# Polarshield_v1_6.net
KiCad netlist of a schematic drawn in EAGLE
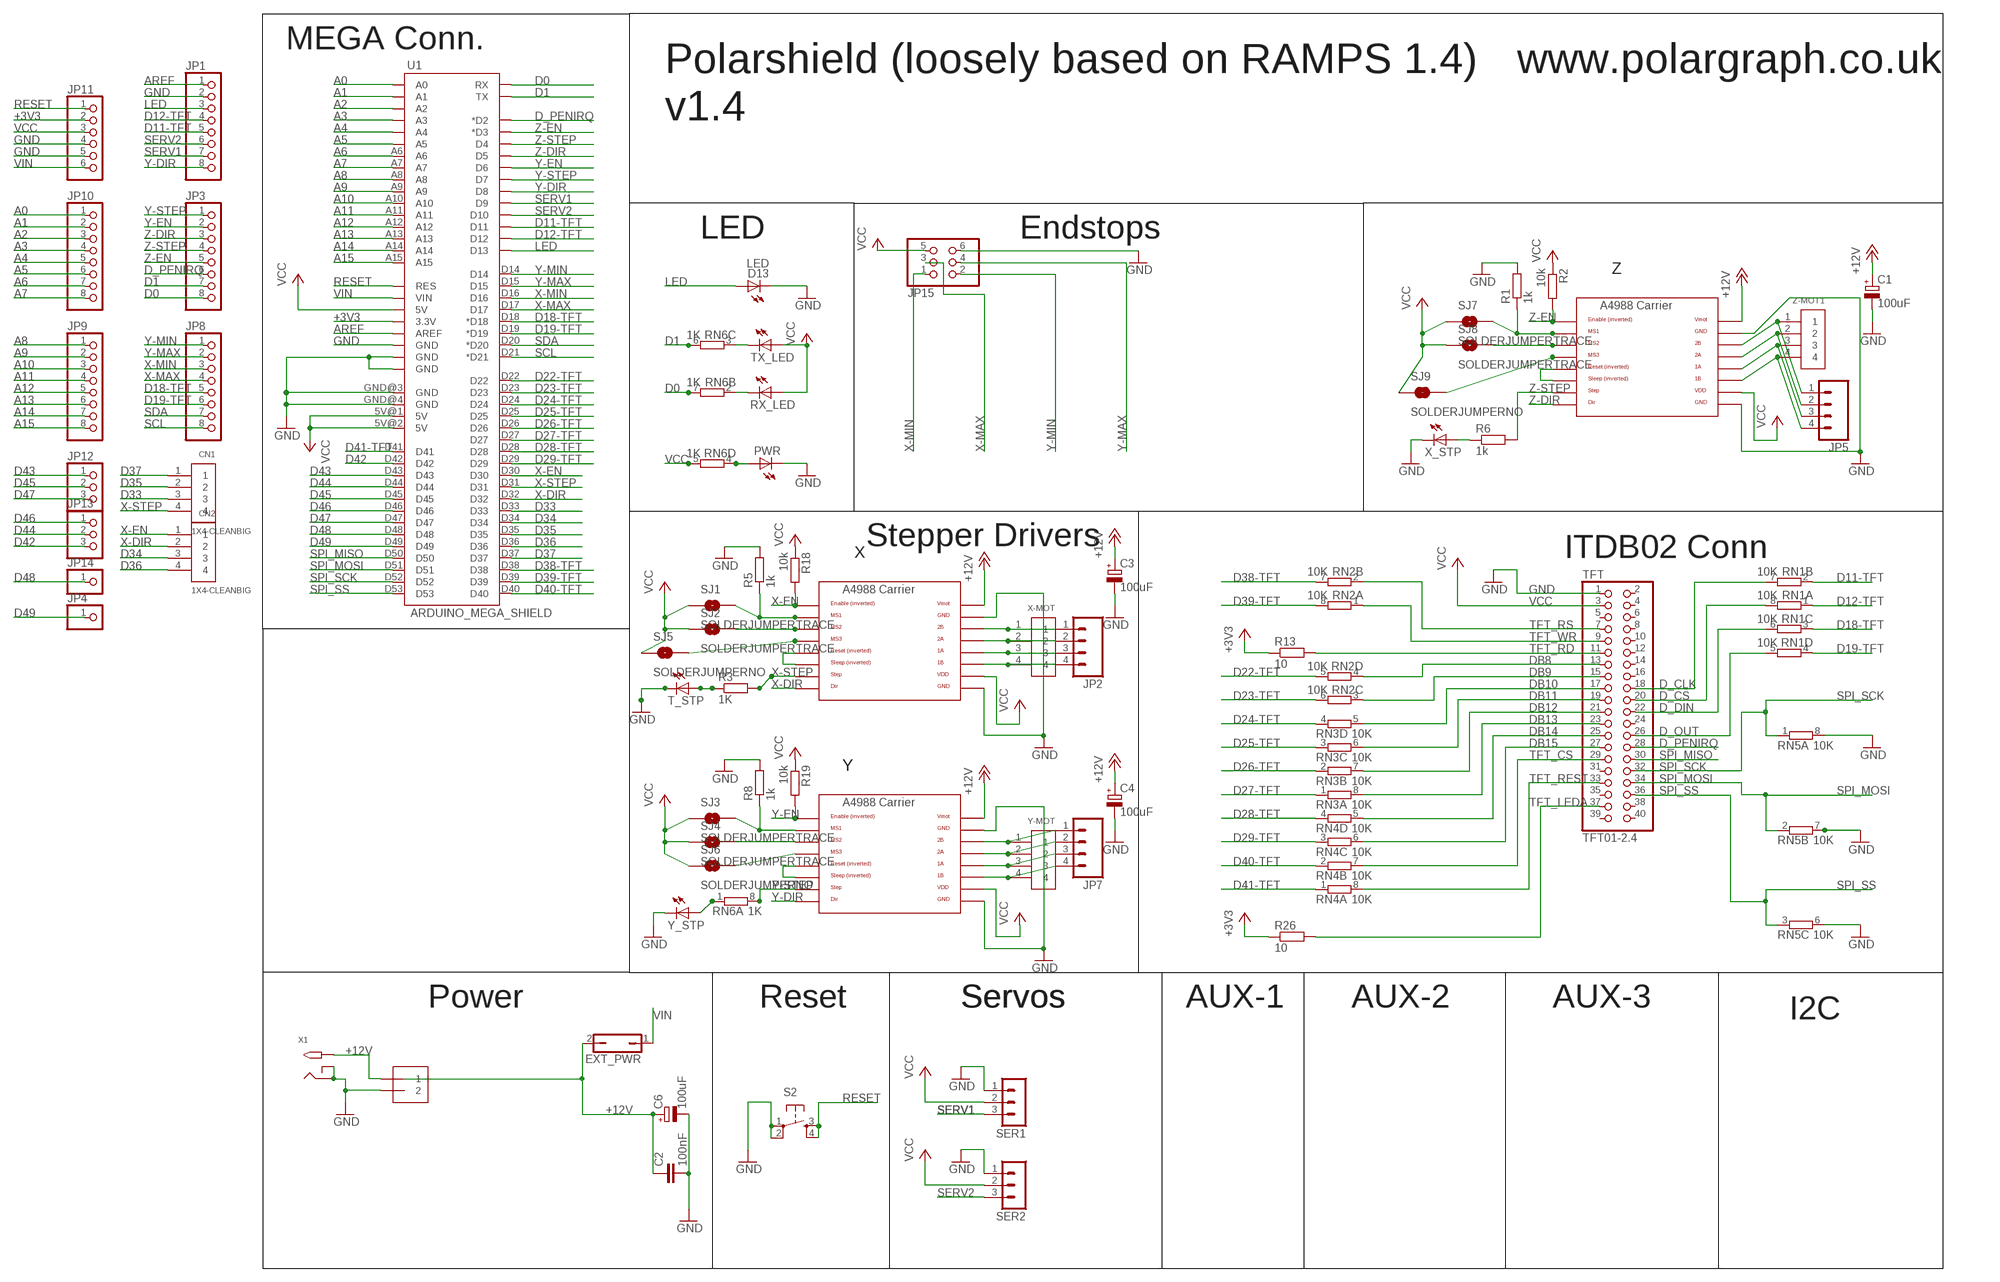
[diagram p0: schematic, sheet 1]

(export (version "E")
  (design (tool "Eeschema 10.0.6"))
  (components
    (comp (ref "C1")
      (value "100uF")
      (footprint "eagle-import:153CLV-0605")
      (libsource (lib "eagle-import") (part "CPOL-EU153CLV-0605"))
    )
    (comp (ref "C2")
      (value "100nF")
      (footprint "eagle-import:C0805")
      (libsource (lib "eagle-import") (part "C-EUC0805"))
    )
    (comp (ref "C3")
      (value "100uF")
      (footprint "eagle-import:153CLV-0605")
      (libsource (lib "eagle-import") (part "CPOL-EU153CLV-0605"))
    )
    (comp (ref "C4")
      (value "100uF")
      (footprint "eagle-import:153CLV-0605")
      (libsource (lib "eagle-import") (part "CPOL-EU153CLV-0605"))
    )
    (comp (ref "C6")
      (value "100uF")
      (footprint "eagle-import:153CLV-0605")
      (libsource (lib "eagle-import") (part "CPOL-EU153CLV-0605"))
    )
    (comp (ref "CN1")
      (value "1X4-CLEANBIG")
      (footprint "eagle-import:1X04-CLEANBIG")
      (libsource (lib "eagle-import") (part "1X4-CLEANBIG"))
    )
    (comp (ref "CN2")
      (value "1X4-CLEANBIG")
      (footprint "eagle-import:1X04-CLEANBIG")
      (libsource (lib "eagle-import") (part "1X4-CLEANBIG"))
    )
    (comp (ref "D13")
      (value "LED")
      (footprint "eagle-import:CHIP-LED0805")
      (libsource (lib "eagle-import") (part "LEDCHIP-LED0805"))
    )
    (comp (ref "EXT_PWR")
      (value "JP1Q")
      (footprint "eagle-import:JP1")
      (libsource (lib "eagle-import") (part "JP1Q"))
    )
    (comp (ref "J1")
      (value "1X2-3.5MM")
      (footprint "eagle-import:1X2-3.5MM")
      (libsource (lib "eagle-import") (part "1X2-3.5MM"))
    )
    (comp (ref "JP1")
      (value "PINHD-1X8CLEANBIG")
      (footprint "eagle-import:1X08-CLEANBIG")
      (libsource (lib "eagle-import") (part "PINHD-1X8CLEANBIG"))
    )
    (comp (ref "JP2")
      (value "M04SCREW")
      (footprint "eagle-import:SCREWTERMINAL-3.5MM-4")
      (libsource (lib "eagle-import") (part "M04SCREW"))
    )
    (comp (ref "JP3")
      (value "PINHD-1X8CLEANBIG")
      (footprint "eagle-import:1X08-CLEANBIG")
      (libsource (lib "eagle-import") (part "PINHD-1X8CLEANBIG"))
    )
    (comp (ref "JP4")
      (value "PINHD-1X1CB")
      (footprint "eagle-import:1X01-CLEANBIG")
      (libsource (lib "eagle-import") (part "PINHD-1X1CB"))
    )
    (comp (ref "JP5")
      (value "M04SCREW")
      (footprint "eagle-import:SCREWTERMINAL-3.5MM-4")
      (libsource (lib "eagle-import") (part "M04SCREW"))
    )
    (comp (ref "JP7")
      (value "M04SCREW")
      (footprint "eagle-import:SCREWTERMINAL-3.5MM-4")
      (libsource (lib "eagle-import") (part "M04SCREW"))
    )
    (comp (ref "JP8")
      (value "PINHD-1X8CLEANBIG")
      (footprint "eagle-import:1X08-CLEANBIG")
      (libsource (lib "eagle-import") (part "PINHD-1X8CLEANBIG"))
    )
    (comp (ref "JP9")
      (value "PINHD-1X8CLEANBIG")
      (footprint "eagle-import:1X08-CLEANBIG")
      (libsource (lib "eagle-import") (part "PINHD-1X8CLEANBIG"))
    )
    (comp (ref "JP10")
      (value "PINHD-1X8CLEANBIG")
      (footprint "eagle-import:1X08-CLEANBIG")
      (libsource (lib "eagle-import") (part "PINHD-1X8CLEANBIG"))
    )
    (comp (ref "JP11")
      (value "PINHD-1X6CB")
      (footprint "eagle-import:1X06-CLEANBIG")
      (libsource (lib "eagle-import") (part "PINHD-1X6CB"))
    )
    (comp (ref "JP12")
      (value "PINHD-1X3CB")
      (footprint "eagle-import:1X03-CLEANBIG")
      (libsource (lib "eagle-import") (part "PINHD-1X3CB"))
    )
    (comp (ref "JP13")
      (value "PINHD-1X3CB")
      (footprint "eagle-import:1X03-CLEANBIG")
      (libsource (lib "eagle-import") (part "PINHD-1X3CB"))
    )
    (comp (ref "JP14")
      (value "PINHD-1X1CB")
      (footprint "eagle-import:1X01-CLEANBIG")
      (libsource (lib "eagle-import") (part "PINHD-1X1CB"))
    )
    (comp (ref "JP15")
      (value "PINHD-2X3")
      (footprint "eagle-import:2X03")
      (libsource (lib "eagle-import") (part "PINHD-2X3"))
    )
    (comp (ref "PWR")
      (value "LEDCHIP-LED0805")
      (footprint "eagle-import:CHIP-LED0805")
      (libsource (lib "eagle-import") (part "LEDCHIP-LED0805"))
    )
    (comp (ref "R1")
      (value "1k")
      (footprint "eagle-import:R0805")
      (libsource (lib "eagle-import") (part "R-EU_R0805"))
    )
    (comp (ref "R2")
      (value "10k")
      (footprint "eagle-import:R0805")
      (libsource (lib "eagle-import") (part "R-EU_R0805"))
    )
    (comp (ref "R3")
      (value "1K")
      (footprint "eagle-import:R0805")
      (libsource (lib "eagle-import") (part "R-EU_R0805"))
    )
    (comp (ref "R5")
      (value "1k")
      (footprint "eagle-import:R0805")
      (libsource (lib "eagle-import") (part "R-EU_R0805"))
    )
    (comp (ref "R6")
      (value "1k")
      (footprint "eagle-import:R0805")
      (libsource (lib "eagle-import") (part "R-EU_R0805"))
    )
    (comp (ref "R8")
      (value "1k")
      (footprint "eagle-import:R0805")
      (libsource (lib "eagle-import") (part "R-EU_R0805"))
    )
    (comp (ref "R13")
      (value "10")
      (footprint "eagle-import:R0805")
      (libsource (lib "eagle-import") (part "resistor_R-EU_R0805"))
    )
    (comp (ref "R18")
      (value "10k")
      (footprint "eagle-import:R0805")
      (libsource (lib "eagle-import") (part "R-EU_R0805"))
    )
    (comp (ref "R19")
      (value "10k")
      (footprint "eagle-import:R0805")
      (libsource (lib "eagle-import") (part "R-EU_R0805"))
    )
    (comp (ref "R26")
      (value "10")
      (footprint "eagle-import:R0805")
      (libsource (lib "eagle-import") (part "resistor_R-EU_R0805"))
    )
    (comp (ref "RN1")
      (value "10K")
      (footprint "eagle-import:EXBS8V")
      (libsource (lib "eagle-import") (part "4R-NEXBS8V"))
    )
    (comp (ref "RN2")
      (value "10K")
      (footprint "eagle-import:EXBS8V")
      (libsource (lib "eagle-import") (part "4R-NEXBS8V"))
    )
    (comp (ref "RN3")
      (value "10K")
      (footprint "eagle-import:EXBS8V")
      (libsource (lib "eagle-import") (part "4R-NEXBS8V"))
    )
    (comp (ref "RN4")
      (value "10K")
      (footprint "eagle-import:EXBS8V")
      (libsource (lib "eagle-import") (part "4R-NEXBS8V"))
    )
    (comp (ref "RN5")
      (value "10K")
      (footprint "eagle-import:EXBS8V")
      (libsource (lib "eagle-import") (part "4R-NEXBS8V"))
    )
    (comp (ref "RN6")
      (value "1K")
      (footprint "eagle-import:EXBS8V")
      (libsource (lib "eagle-import") (part "4R-NEXBS8V"))
    )
    (comp (ref "RX_LED")
      (value "LEDCHIP-LED0805")
      (footprint "eagle-import:CHIP-LED0805")
      (libsource (lib "eagle-import") (part "LEDCHIP-LED0805"))
    )
    (comp (ref "S2")
      (value "TAC_SWITCHPTH")
      (footprint "eagle-import:TACTILE-PTH")
      (libsource (lib "eagle-import") (part "TAC_SWITCHPTH"))
    )
    (comp (ref "SER1")
      (value "3PIN-HEADER")
      (footprint "eagle-import:3PIN-HEADER")
      (libsource (lib "eagle-import") (part "3PIN-HEADER"))
    )
    (comp (ref "SER2")
      (value "3PIN-HEADER")
      (footprint "eagle-import:3PIN-HEADER")
      (libsource (lib "eagle-import") (part "3PIN-HEADER"))
    )
    (comp (ref "SJ1")
      (value "SOLDERJUMPERTRACE")
      (footprint "eagle-import:SJ_2S-TRACE")
      (libsource (lib "eagle-import") (part "SOLDERJUMPERTRACE"))
    )
    (comp (ref "SJ2")
      (value "SOLDERJUMPERTRACE")
      (footprint "eagle-import:SJ_2S-TRACE")
      (libsource (lib "eagle-import") (part "SOLDERJUMPERTRACE"))
    )
    (comp (ref "SJ3")
      (value "SOLDERJUMPERTRACE")
      (footprint "eagle-import:SJ_2S-TRACE")
      (libsource (lib "eagle-import") (part "SOLDERJUMPERTRACE"))
    )
    (comp (ref "SJ4")
      (value "SOLDERJUMPERTRACE")
      (footprint "eagle-import:SJ_2S-TRACE")
      (libsource (lib "eagle-import") (part "SOLDERJUMPERTRACE"))
    )
    (comp (ref "SJ5")
      (value "SOLDERJUMPERNO")
      (footprint "eagle-import:SJ_2S-NO")
      (libsource (lib "eagle-import") (part "SOLDERJUMPERNO"))
    )
    (comp (ref "SJ6")
      (value "SOLDERJUMPERNO")
      (footprint "eagle-import:SJ_2S-NO")
      (libsource (lib "eagle-import") (part "SOLDERJUMPERNO"))
    )
    (comp (ref "SJ7")
      (value "SOLDERJUMPERTRACE")
      (footprint "eagle-import:SJ_2S-TRACE")
      (libsource (lib "eagle-import") (part "SOLDERJUMPERTRACE"))
    )
    (comp (ref "SJ8")
      (value "SOLDERJUMPERTRACE")
      (footprint "eagle-import:SJ_2S-TRACE")
      (libsource (lib "eagle-import") (part "SOLDERJUMPERTRACE"))
    )
    (comp (ref "SJ9")
      (value "SOLDERJUMPERNO")
      (footprint "eagle-import:SJ_2S-NO")
      (libsource (lib "eagle-import") (part "SOLDERJUMPERNO"))
    )
    (comp (ref "TFT")
      (value "TFT01-2.4")
      (footprint "eagle-import:TFT01-2.4")
      (libsource (lib "eagle-import") (part "TFT01-2.4"))
    )
    (comp (ref "TX_LED")
      (value "LEDCHIP-LED0805")
      (footprint "eagle-import:CHIP-LED0805")
      (libsource (lib "eagle-import") (part "LEDCHIP-LED0805"))
    )
    (comp (ref "T_STP")
      (value "LEDCHIP-LED0805")
      (footprint "eagle-import:CHIP-LED0805")
      (libsource (lib "eagle-import") (part "LEDCHIP-LED0805"))
    )
    (comp (ref "U$1")
      (value "A4988BREAKOUT")
      (footprint "eagle-import:A4988BREAKOUT")
      (libsource (lib "eagle-import") (part "A4988BREAKOUT"))
    )
    (comp (ref "U$6")
      (value "A4988BREAKOUT")
      (footprint "eagle-import:A4988BREAKOUT")
      (libsource (lib "eagle-import") (part "A4988BREAKOUT"))
    )
    (comp (ref "U$7")
      (value "A4988BREAKOUT")
      (footprint "eagle-import:A4988BREAKOUT")
      (libsource (lib "eagle-import") (part "A4988BREAKOUT"))
    )
    (comp (ref "U1")
      (value "ARDUINO_MEGA_SHIELD")
      (footprint "eagle-import:ARDUINO_MEGA_SHIELD")
      (libsource (lib "eagle-import") (part "ARDUINO_MEGA_SHIELD"))
    )
    (comp (ref "X-MOT")
      (value "1X4-BIG")
      (footprint "eagle-import:1X04-BIG")
      (libsource (lib "eagle-import") (part "1X4-BIG"))
    )
    (comp (ref "X1")
      (value "2.1MMJACKTHM")
      (footprint "eagle-import:PJ-102A")
      (libsource (lib "eagle-import") (part "2.1MMJACKTHM"))
    )
    (comp (ref "X_STP")
      (value "LEDCHIP-LED0805")
      (footprint "eagle-import:CHIP-LED0805")
      (libsource (lib "eagle-import") (part "LEDCHIP-LED0805"))
    )
    (comp (ref "Y-MOT")
      (value "1X4-BIG")
      (footprint "eagle-import:1X04-BIG")
      (libsource (lib "eagle-import") (part "1X4-BIG"))
    )
    (comp (ref "Y_STP")
      (value "LEDCHIP-LED0805")
      (footprint "eagle-import:CHIP-LED0805")
      (libsource (lib "eagle-import") (part "LEDCHIP-LED0805"))
    )
    (comp (ref "Z-MOT1")
      (value "1X4-BIG")
      (footprint "eagle-import:1X04-BIG")
      (libsource (lib "eagle-import") (part "1X4-BIG"))
    )
  )
  (nets
    (net (code "1") (name "+3V3") (class "Default")
      (node (ref "JP11") (pin "2") (pinfunction "2_2") (pintype "passive"))
      (node (ref "R13") (pin "1") (pinfunction "1_1") (pintype "passive"))
      (node (ref "R26") (pin "1") (pinfunction "1_1") (pintype "passive"))
      (node (ref "U1") (pin "3.3V") (pinfunction "3.3V_3.3V") (pintype "bidirectional"))
    )
    (net (code "2") (name "+12V") (class "Default")
      (node (ref "C1") (pin "+") (pinfunction "+_+") (pintype "passive"))
      (node (ref "C2") (pin "1") (pinfunction "1_1") (pintype "passive"))
      (node (ref "C3") (pin "+") (pinfunction "+_+") (pintype "passive"))
      (node (ref "C4") (pin "+") (pinfunction "+_+") (pintype "passive"))
      (node (ref "C6") (pin "+") (pinfunction "+_+") (pintype "passive"))
      (node (ref "EXT_PWR") (pin "2") (pinfunction "2_2") (pintype "passive"))
      (node (ref "J1") (pin "1") (pinfunction "1_1") (pintype "passive"))
      (node (ref "U$1") (pin "VMOT") (pinfunction "VMOT_VMOT") (pintype "power_in"))
      (node (ref "U$6") (pin "VMOT") (pinfunction "VMOT_VMOT") (pintype "power_in"))
      (node (ref "U$7") (pin "VMOT") (pinfunction "VMOT_VMOT") (pintype "power_in"))
      (node (ref "X1") (pin "TIP") (pinfunction "TIP_TIP") (pintype "bidirectional"))
    )
    (net (code "3") (name "/A0") (class "Default")
      (node (ref "JP10") (pin "1") (pinfunction "1_1") (pintype "passive"))
      (node (ref "U1") (pin "A0") (pinfunction "A0_A0") (pintype "bidirectional"))
    )
    (net (code "4") (name "/A1") (class "Default")
      (node (ref "JP10") (pin "2") (pinfunction "2_2") (pintype "passive"))
      (node (ref "U1") (pin "A1") (pinfunction "A1_A1") (pintype "bidirectional"))
    )
    (net (code "5") (name "/A2") (class "Default")
      (node (ref "JP10") (pin "3") (pinfunction "3_3") (pintype "passive"))
      (node (ref "U1") (pin "A2") (pinfunction "A2_A2") (pintype "bidirectional"))
    )
    (net (code "6") (name "/A3") (class "Default")
      (node (ref "JP10") (pin "4") (pinfunction "4_4") (pintype "passive"))
      (node (ref "U1") (pin "A3") (pinfunction "A3_A3") (pintype "bidirectional"))
    )
    (net (code "7") (name "/A4") (class "Default")
      (node (ref "JP10") (pin "5") (pinfunction "5_5") (pintype "passive"))
      (node (ref "U1") (pin "A4") (pinfunction "A4_A4") (pintype "bidirectional"))
    )
    (net (code "8") (name "/A5") (class "Default")
      (node (ref "JP10") (pin "6") (pinfunction "6_6") (pintype "passive"))
      (node (ref "U1") (pin "A5") (pinfunction "A5_A5") (pintype "bidirectional"))
    )
    (net (code "9") (name "/A6") (class "Default")
      (node (ref "JP10") (pin "7") (pinfunction "7_7") (pintype "passive"))
      (node (ref "U1") (pin "A6") (pinfunction "A6_A6") (pintype "bidirectional"))
    )
    (net (code "10") (name "/A7") (class "Default")
      (node (ref "JP10") (pin "8") (pinfunction "8_8") (pintype "passive"))
      (node (ref "U1") (pin "A7") (pinfunction "A7_A7") (pintype "bidirectional"))
    )
    (net (code "11") (name "/A8") (class "Default")
      (node (ref "JP9") (pin "1") (pinfunction "1_1") (pintype "passive"))
      (node (ref "U1") (pin "A8") (pinfunction "A8_A8") (pintype "bidirectional"))
    )
    (net (code "12") (name "/A9") (class "Default")
      (node (ref "JP9") (pin "2") (pinfunction "2_2") (pintype "passive"))
      (node (ref "U1") (pin "A9") (pinfunction "A9_A9") (pintype "bidirectional"))
    )
    (net (code "13") (name "/A10") (class "Default")
      (node (ref "JP9") (pin "3") (pinfunction "3_3") (pintype "passive"))
      (node (ref "U1") (pin "A10") (pinfunction "A10_A10") (pintype "bidirectional"))
    )
    (net (code "14") (name "/A11") (class "Default")
      (node (ref "JP9") (pin "4") (pinfunction "4_4") (pintype "passive"))
      (node (ref "U1") (pin "A11") (pinfunction "A11_A11") (pintype "bidirectional"))
    )
    (net (code "15") (name "/A12") (class "Default")
      (node (ref "JP9") (pin "5") (pinfunction "5_5") (pintype "passive"))
      (node (ref "U1") (pin "A12") (pinfunction "A12_A12") (pintype "bidirectional"))
    )
    (net (code "16") (name "/A13") (class "Default")
      (node (ref "JP9") (pin "6") (pinfunction "6_6") (pintype "passive"))
      (node (ref "U1") (pin "A13") (pinfunction "A13_A13") (pintype "bidirectional"))
    )
    (net (code "17") (name "/A14") (class "Default")
      (node (ref "JP9") (pin "7") (pinfunction "7_7") (pintype "passive"))
      (node (ref "U1") (pin "A14") (pinfunction "A14_A14") (pintype "bidirectional"))
    )
    (net (code "18") (name "/A15") (class "Default")
      (node (ref "JP9") (pin "8") (pinfunction "8_8") (pintype "passive"))
      (node (ref "U1") (pin "A15") (pinfunction "A15_A15") (pintype "bidirectional"))
    )
    (net (code "19") (name "/AREF") (class "Default")
      (node (ref "JP1") (pin "1") (pinfunction "1_1") (pintype "passive"))
      (node (ref "U1") (pin "AREF") (pinfunction "AREF_AREF") (pintype "bidirectional"))
    )
    (net (code "20") (name "/D0") (class "Default")
      (node (ref "JP3") (pin "8") (pinfunction "8_8") (pintype "passive"))
      (node (ref "RN6") (pin "7") (pinfunction "2_7") (pintype "passive"))
      (node (ref "U1") (pin "RX") (pinfunction "RX_RX") (pintype "bidirectional"))
    )
    (net (code "21") (name "/D1") (class "Default")
      (node (ref "JP3") (pin "7") (pinfunction "7_7") (pintype "passive"))
      (node (ref "RN6") (pin "6") (pinfunction "2_6") (pintype "passive"))
      (node (ref "U1") (pin "TX") (pinfunction "TX_TX") (pintype "bidirectional"))
    )
    (net (code "22") (name "/D11-TFT") (class "Default")
      (node (ref "JP1") (pin "5") (pinfunction "5_5") (pintype "passive"))
      (node (ref "RN1") (pin "2") (pinfunction "1_2") (pintype "passive"))
      (node (ref "U1") (pin "D11") (pinfunction "D11_D11") (pintype "bidirectional"))
    )
    (net (code "23") (name "/D12-TFT") (class "Default")
      (node (ref "JP1") (pin "4") (pinfunction "4_4") (pintype "passive"))
      (node (ref "RN1") (pin "1") (pinfunction "1_1") (pintype "passive"))
      (node (ref "U1") (pin "D12") (pinfunction "D12_D12") (pintype "bidirectional"))
    )
    (net (code "24") (name "/D18-TFT") (class "Default")
      (node (ref "JP8") (pin "5") (pinfunction "5_5") (pintype "passive"))
      (node (ref "RN1") (pin "3") (pinfunction "1_3") (pintype "passive"))
      (node (ref "U1") (pin "D18") (pinfunction "*D18_D18") (pintype "bidirectional"))
    )
    (net (code "25") (name "/D19-TFT") (class "Default")
      (node (ref "JP8") (pin "6") (pinfunction "6_6") (pintype "passive"))
      (node (ref "RN1") (pin "4") (pinfunction "1_4") (pintype "passive"))
      (node (ref "U1") (pin "D19") (pinfunction "*D19_D19") (pintype "bidirectional"))
    )
    (net (code "26") (name "/D22-TFT") (class "Default")
      (node (ref "RN2") (pin "5") (pinfunction "2_5") (pintype "passive"))
      (node (ref "U1") (pin "D22") (pinfunction "D22_D22") (pintype "bidirectional"))
    )
    (net (code "27") (name "/D23-TFT") (class "Default")
      (node (ref "RN2") (pin "6") (pinfunction "2_6") (pintype "passive"))
      (node (ref "U1") (pin "D23") (pinfunction "D23_D23") (pintype "bidirectional"))
    )
    (net (code "28") (name "/D24-TFT") (class "Default")
      (node (ref "RN3") (pin "4") (pinfunction "1_4") (pintype "passive"))
      (node (ref "U1") (pin "D24") (pinfunction "D24_D24") (pintype "bidirectional"))
    )
    (net (code "29") (name "/D25-TFT") (class "Default")
      (node (ref "RN3") (pin "3") (pinfunction "1_3") (pintype "passive"))
      (node (ref "U1") (pin "D25") (pinfunction "D25_D25") (pintype "bidirectional"))
    )
    (net (code "30") (name "/D26-TFT") (class "Default")
      (node (ref "RN3") (pin "2") (pinfunction "1_2") (pintype "passive"))
      (node (ref "U1") (pin "D26") (pinfunction "D26_D26") (pintype "bidirectional"))
    )
    (net (code "31") (name "/D27-TFT") (class "Default")
      (node (ref "RN3") (pin "1") (pinfunction "1_1") (pintype "passive"))
      (node (ref "U1") (pin "D27") (pinfunction "D27_D27") (pintype "bidirectional"))
    )
    (net (code "32") (name "/D28-TFT") (class "Default")
      (node (ref "RN4") (pin "4") (pinfunction "1_4") (pintype "passive"))
      (node (ref "U1") (pin "D28") (pinfunction "D28_D28") (pintype "bidirectional"))
    )
    (net (code "33") (name "/D29-TFT") (class "Default")
      (node (ref "RN4") (pin "3") (pinfunction "1_3") (pintype "passive"))
      (node (ref "U1") (pin "D29") (pinfunction "D29_D29") (pintype "bidirectional"))
    )
    (net (code "34") (name "/D33") (class "Default")
      (node (ref "CN1") (pin "3") (pinfunction "3_3") (pintype "bidirectional"))
      (node (ref "U1") (pin "D33") (pinfunction "D33_D33") (pintype "bidirectional"))
    )
    (net (code "35") (name "/D34") (class "Default")
      (node (ref "CN2") (pin "3") (pinfunction "3_3") (pintype "bidirectional"))
      (node (ref "U1") (pin "D34") (pinfunction "D34_D34") (pintype "bidirectional"))
    )
    (net (code "36") (name "/D35") (class "Default")
      (node (ref "CN1") (pin "2") (pinfunction "2_2") (pintype "bidirectional"))
      (node (ref "U1") (pin "D35") (pinfunction "D35_D35") (pintype "bidirectional"))
    )
    (net (code "37") (name "/D36") (class "Default")
      (node (ref "CN2") (pin "4") (pinfunction "4_4") (pintype "bidirectional"))
      (node (ref "U1") (pin "D36") (pinfunction "D36_D36") (pintype "bidirectional"))
    )
    (net (code "38") (name "/D37") (class "Default")
      (node (ref "CN1") (pin "1") (pinfunction "1_1") (pintype "bidirectional"))
      (node (ref "U1") (pin "D37") (pinfunction "D37_D37") (pintype "bidirectional"))
    )
    (net (code "39") (name "/D38-TFT") (class "Default")
      (node (ref "RN2") (pin "7") (pinfunction "2_7") (pintype "passive"))
      (node (ref "U1") (pin "D38") (pinfunction "D38_D38") (pintype "bidirectional"))
    )
    (net (code "40") (name "/D39-TFT") (class "Default")
      (node (ref "RN2") (pin "8") (pinfunction "2_8") (pintype "passive"))
      (node (ref "U1") (pin "D39") (pinfunction "D39_D39") (pintype "bidirectional"))
    )
    (net (code "41") (name "/D40-TFT") (class "Default")
      (node (ref "RN4") (pin "2") (pinfunction "1_2") (pintype "passive"))
      (node (ref "U1") (pin "D40") (pinfunction "D40_D40") (pintype "bidirectional"))
    )
    (net (code "42") (name "/D41-TFT") (class "Default")
      (node (ref "RN4") (pin "1") (pinfunction "1_1") (pintype "passive"))
      (node (ref "U1") (pin "D41") (pinfunction "D41_D41") (pintype "bidirectional"))
    )
    (net (code "43") (name "/D42") (class "Default")
      (node (ref "JP13") (pin "3") (pinfunction "3_3") (pintype "passive"))
      (node (ref "U1") (pin "D42") (pinfunction "D42_D42") (pintype "bidirectional"))
    )
    (net (code "44") (name "/D43") (class "Default")
      (node (ref "JP12") (pin "1") (pinfunction "1_1") (pintype "passive"))
      (node (ref "U1") (pin "D43") (pinfunction "D43_D43") (pintype "bidirectional"))
    )
    (net (code "45") (name "/D44") (class "Default")
      (node (ref "JP13") (pin "2") (pinfunction "2_2") (pintype "passive"))
      (node (ref "U1") (pin "D44") (pinfunction "D44_D44") (pintype "bidirectional"))
    )
    (net (code "46") (name "/D45") (class "Default")
      (node (ref "JP12") (pin "2") (pinfunction "2_2") (pintype "passive"))
      (node (ref "U1") (pin "D45") (pinfunction "D45_D45") (pintype "bidirectional"))
    )
    (net (code "47") (name "/D46") (class "Default")
      (node (ref "JP13") (pin "1") (pinfunction "1_1") (pintype "passive"))
      (node (ref "U1") (pin "D46") (pinfunction "D46_D46") (pintype "bidirectional"))
    )
    (net (code "48") (name "/D47") (class "Default")
      (node (ref "JP12") (pin "3") (pinfunction "3_3") (pintype "passive"))
      (node (ref "U1") (pin "D47") (pinfunction "D47_D47") (pintype "bidirectional"))
    )
    (net (code "49") (name "/D48") (class "Default")
      (node (ref "JP14") (pin "1") (pinfunction "1_1") (pintype "passive"))
      (node (ref "U1") (pin "D48") (pinfunction "D48_D48") (pintype "bidirectional"))
    )
    (net (code "50") (name "/D49") (class "Default")
      (node (ref "JP4") (pin "1") (pinfunction "1_1") (pintype "passive"))
      (node (ref "U1") (pin "D49") (pinfunction "D49_D49") (pintype "bidirectional"))
    )
    (net (code "51") (name "/DB8") (class "Default")
      (node (ref "RN2") (pin "4") (pinfunction "1_4") (pintype "passive"))
      (node (ref "TFT") (pin "13") (pinfunction "13_13") (pintype "passive"))
    )
    (net (code "52") (name "/DB9") (class "Default")
      (node (ref "RN2") (pin "3") (pinfunction "1_3") (pintype "passive"))
      (node (ref "TFT") (pin "15") (pinfunction "15_15") (pintype "passive"))
    )
    (net (code "53") (name "/DB10") (class "Default")
      (node (ref "RN3") (pin "5") (pinfunction "2_5") (pintype "passive"))
      (node (ref "TFT") (pin "17") (pinfunction "17_17") (pintype "passive"))
    )
    (net (code "54") (name "/DB11") (class "Default")
      (node (ref "RN3") (pin "6") (pinfunction "2_6") (pintype "passive"))
      (node (ref "TFT") (pin "19") (pinfunction "19_19") (pintype "passive"))
    )
    (net (code "55") (name "/DB12") (class "Default")
      (node (ref "RN3") (pin "7") (pinfunction "2_7") (pintype "passive"))
      (node (ref "TFT") (pin "21") (pinfunction "21_21") (pintype "passive"))
    )
    (net (code "56") (name "/DB13") (class "Default")
      (node (ref "RN3") (pin "8") (pinfunction "2_8") (pintype "passive"))
      (node (ref "TFT") (pin "23") (pinfunction "23_23") (pintype "passive"))
    )
    (net (code "57") (name "/DB14") (class "Default")
      (node (ref "RN4") (pin "5") (pinfunction "2_5") (pintype "passive"))
      (node (ref "TFT") (pin "25") (pinfunction "25_25") (pintype "passive"))
    )
    (net (code "58") (name "/DB15") (class "Default")
      (node (ref "RN4") (pin "6") (pinfunction "2_6") (pintype "passive"))
      (node (ref "TFT") (pin "27") (pinfunction "27_27") (pintype "passive"))
    )
    (net (code "59") (name "/D_CLK") (class "Default")
      (node (ref "RN1") (pin "7") (pinfunction "2_7") (pintype "passive"))
      (node (ref "TFT") (pin "18") (pinfunction "18_18") (pintype "passive"))
    )
    (net (code "60") (name "/D_CS") (class "Default")
      (node (ref "RN1") (pin "8") (pinfunction "2_8") (pintype "passive"))
      (node (ref "TFT") (pin "20") (pinfunction "20_20") (pintype "passive"))
    )
    (net (code "61") (name "/D_DIN") (class "Default")
      (node (ref "RN1") (pin "6") (pinfunction "2_6") (pintype "passive"))
      (node (ref "TFT") (pin "22") (pinfunction "22_22") (pintype "passive"))
    )
    (net (code "62") (name "/D_OUT") (class "Default")
      (node (ref "RN1") (pin "5") (pinfunction "2_5") (pintype "passive"))
      (node (ref "TFT") (pin "26") (pinfunction "26_26") (pintype "passive"))
    )
    (net (code "63") (name "/D_PENIRQ") (class "Default")
      (node (ref "JP3") (pin "6") (pinfunction "6_6") (pintype "passive"))
      (node (ref "TFT") (pin "28") (pinfunction "28_28") (pintype "passive"))
      (node (ref "U1") (pin "D2") (pinfunction "*D2_D2") (pintype "bidirectional"))
    )
    (net (code "64") (name "/LED") (class "Default")
      (node (ref "D13") (pin "A") (pinfunction "A_A") (pintype "passive"))
      (node (ref "JP1") (pin "3") (pinfunction "3_3") (pintype "passive"))
      (node (ref "U1") (pin "D13") (pinfunction "D13_D13") (pintype "bidirectional"))
    )
    (net (code "65") (name "/RESET") (class "Default")
      (node (ref "JP11") (pin "1") (pinfunction "1_1") (pintype "passive"))
      (node (ref "S2") (pin "3") (pinfunction "3_3") (pintype "passive"))
      (node (ref "S2") (pin "4") (pinfunction "4_4") (pintype "passive"))
      (node (ref "U1") (pin "RES") (pinfunction "RES_RES") (pintype "bidirectional"))
    )
    (net (code "66") (name "/SCL") (class "Default")
      (node (ref "JP8") (pin "8") (pinfunction "8_8") (pintype "passive"))
      (node (ref "U1") (pin "D21") (pinfunction "*D21_D21") (pintype "bidirectional"))
    )
    (net (code "67") (name "/SDA") (class "Default")
      (node (ref "JP8") (pin "7") (pinfunction "7_7") (pintype "passive"))
      (node (ref "U1") (pin "D20") (pinfunction "*D20_D20") (pintype "bidirectional"))
    )
    (net (code "68") (name "/SERV1") (class "Default")
      (node (ref "JP1") (pin "7") (pinfunction "7_7") (pintype "passive"))
      (node (ref "SER1") (pin "3") (pinfunction "3_3") (pintype "passive"))
      (node (ref "U1") (pin "D9") (pinfunction "D9_D9") (pintype "bidirectional"))
    )
    (net (code "69") (name "/SERV2") (class "Default")
      (node (ref "JP1") (pin "6") (pinfunction "6_6") (pintype "passive"))
      (node (ref "SER2") (pin "3") (pinfunction "3_3") (pintype "passive"))
      (node (ref "U1") (pin "D10") (pinfunction "D10_D10") (pintype "bidirectional"))
    )
    (net (code "70") (name "/SPI_MISO") (class "Default")
      (node (ref "TFT") (pin "30") (pinfunction "30_30") (pintype "passive"))
      (node (ref "U1") (pin "D50") (pinfunction "D50_D50") (pintype "bidirectional"))
    )
    (net (code "71") (name "/SPI_MOSI") (class "Default")
      (node (ref "RN5") (pin "2") (pinfunction "1_2") (pintype "passive"))
      (node (ref "TFT") (pin "34") (pinfunction "34_34") (pintype "passive"))
      (node (ref "U1") (pin "D51") (pinfunction "D51_D51") (pintype "bidirectional"))
    )
    (net (code "72") (name "/SPI_SCK") (class "Default")
      (node (ref "RN5") (pin "1") (pinfunction "1_1") (pintype "passive"))
      (node (ref "TFT") (pin "32") (pinfunction "32_32") (pintype "passive"))
      (node (ref "U1") (pin "D52") (pinfunction "D52_D52") (pintype "bidirectional"))
    )
    (net (code "73") (name "/SPI_SS") (class "Default")
      (node (ref "RN5") (pin "3") (pinfunction "1_3") (pintype "passive"))
      (node (ref "TFT") (pin "36") (pinfunction "36_36") (pintype "passive"))
      (node (ref "U1") (pin "D53") (pinfunction "D53_D53") (pintype "bidirectional"))
    )
    (net (code "74") (name "/TFT_CS") (class "Default")
      (node (ref "RN4") (pin "7") (pinfunction "2_7") (pintype "passive"))
      (node (ref "TFT") (pin "29") (pinfunction "29_29") (pintype "passive"))
    )
    (net (code "75") (name "/TFT_LEDA") (class "Default")
      (node (ref "R26") (pin "2") (pinfunction "2_2") (pintype "passive"))
      (node (ref "TFT") (pin "37") (pinfunction "37_37") (pintype "passive"))
    )
    (net (code "76") (name "/TFT_RD") (class "Default")
      (node (ref "R13") (pin "2") (pinfunction "2_2") (pintype "passive"))
      (node (ref "TFT") (pin "11") (pinfunction "11_11") (pintype "passive"))
    )
    (net (code "77") (name "/TFT_REST") (class "Default")
      (node (ref "RN4") (pin "8") (pinfunction "2_8") (pintype "passive"))
      (node (ref "TFT") (pin "33") (pinfunction "33_33") (pintype "passive"))
    )
    (net (code "78") (name "/TFT_RS") (class "Default")
      (node (ref "RN2") (pin "2") (pinfunction "1_2") (pintype "passive"))
      (node (ref "TFT") (pin "7") (pinfunction "7_7") (pintype "passive"))
    )
    (net (code "79") (name "/TFT_WR") (class "Default")
      (node (ref "RN2") (pin "1") (pinfunction "1_1") (pintype "passive"))
      (node (ref "TFT") (pin "9") (pinfunction "9_9") (pintype "passive"))
    )
    (net (code "80") (name "/VIN") (class "Default")
      (node (ref "EXT_PWR") (pin "1") (pinfunction "1_1") (pintype "passive"))
      (node (ref "JP11") (pin "6") (pinfunction "6_6") (pintype "passive"))
      (node (ref "U1") (pin "VIN") (pinfunction "VIN_VIN") (pintype "bidirectional"))
    )
    (net (code "81") (name "/X-DIR") (class "Default")
      (node (ref "CN2") (pin "2") (pinfunction "2_2") (pintype "bidirectional"))
      (node (ref "U$6") (pin "DIR") (pinfunction "DIR_DIR") (pintype "input"))
      (node (ref "U1") (pin "D32") (pinfunction "D32_D32") (pintype "bidirectional"))
    )
    (net (code "82") (name "/X-EN") (class "Default")
      (node (ref "CN2") (pin "1") (pinfunction "1_1") (pintype "bidirectional"))
      (node (ref "R18") (pin "2") (pinfunction "2_2") (pintype "passive"))
      (node (ref "U$6") (pin "EN") (pinfunction "EN_EN") (pintype "input"))
      (node (ref "U1") (pin "D30") (pinfunction "D30_D30") (pintype "bidirectional"))
    )
    (net (code "83") (name "/X-MAX") (class "Default")
      (node (ref "JP15") (pin "3") (pinfunction "3_3") (pintype "passive"))
      (node (ref "JP8") (pin "4") (pinfunction "4_4") (pintype "passive"))
      (node (ref "U1") (pin "D17") (pinfunction "D17_D17") (pintype "bidirectional"))
    )
    (net (code "84") (name "/X-MIN") (class "Default")
      (node (ref "JP15") (pin "1") (pinfunction "1_1") (pintype "passive"))
      (node (ref "JP8") (pin "3") (pinfunction "3_3") (pintype "passive"))
      (node (ref "U1") (pin "D16") (pinfunction "D16_D16") (pintype "bidirectional"))
    )
    (net (code "85") (name "/X-STEP") (class "Default")
      (node (ref "CN1") (pin "4") (pinfunction "4_4") (pintype "bidirectional"))
      (node (ref "R3") (pin "2") (pinfunction "2_2") (pintype "passive"))
      (node (ref "U$6") (pin "STEP") (pinfunction "STEP_STEP") (pintype "input"))
      (node (ref "U1") (pin "D31") (pinfunction "D31_D31") (pintype "bidirectional"))
    )
    (net (code "86") (name "/Y-DIR") (class "Default")
      (node (ref "JP1") (pin "8") (pinfunction "8_8") (pintype "passive"))
      (node (ref "U$7") (pin "DIR") (pinfunction "DIR_DIR") (pintype "input"))
      (node (ref "U1") (pin "D8") (pinfunction "D8_D8") (pintype "bidirectional"))
    )
    (net (code "87") (name "/Y-EN") (class "Default")
      (node (ref "JP3") (pin "2") (pinfunction "2_2") (pintype "passive"))
      (node (ref "R19") (pin "2") (pinfunction "2_2") (pintype "passive"))
      (node (ref "U$7") (pin "EN") (pinfunction "EN_EN") (pintype "input"))
      (node (ref "U1") (pin "D6") (pinfunction "D6_D6") (pintype "bidirectional"))
    )
    (net (code "88") (name "/Y-MAX") (class "Default")
      (node (ref "JP15") (pin "4") (pinfunction "4_4") (pintype "passive"))
      (node (ref "JP8") (pin "2") (pinfunction "2_2") (pintype "passive"))
      (node (ref "U1") (pin "D15") (pinfunction "D15_D15") (pintype "bidirectional"))
    )
    (net (code "89") (name "/Y-MIN") (class "Default")
      (node (ref "JP15") (pin "2") (pinfunction "2_2") (pintype "passive"))
      (node (ref "JP8") (pin "1") (pinfunction "1_1") (pintype "passive"))
      (node (ref "U1") (pin "D14") (pinfunction "D14_D14") (pintype "bidirectional"))
    )
    (net (code "90") (name "/Y-STEP") (class "Default")
      (node (ref "JP3") (pin "1") (pinfunction "1_1") (pintype "passive"))
      (node (ref "RN6") (pin "8") (pinfunction "2_8") (pintype "passive"))
      (node (ref "U$7") (pin "STEP") (pinfunction "STEP_STEP") (pintype "input"))
      (node (ref "U1") (pin "D7") (pinfunction "D7_D7") (pintype "bidirectional"))
    )
    (net (code "91") (name "/Z-DIR") (class "Default")
      (node (ref "JP3") (pin "3") (pinfunction "3_3") (pintype "passive"))
      (node (ref "U$1") (pin "DIR") (pinfunction "DIR_DIR") (pintype "input"))
      (node (ref "U1") (pin "D5") (pinfunction "D5_D5") (pintype "bidirectional"))
    )
    (net (code "92") (name "/Z-EN") (class "Default")
      (node (ref "JP3") (pin "5") (pinfunction "5_5") (pintype "passive"))
      (node (ref "R2") (pin "2") (pinfunction "2_2") (pintype "passive"))
      (node (ref "U$1") (pin "EN") (pinfunction "EN_EN") (pintype "input"))
      (node (ref "U1") (pin "D3") (pinfunction "*D3_D3") (pintype "bidirectional"))
    )
    (net (code "93") (name "/Z-STEP") (class "Default")
      (node (ref "JP3") (pin "4") (pinfunction "4_4") (pintype "passive"))
      (node (ref "R6") (pin "2") (pinfunction "2_2") (pintype "passive"))
      (node (ref "U$1") (pin "STEP") (pinfunction "STEP_STEP") (pintype "input"))
      (node (ref "U1") (pin "D4") (pinfunction "D4_D4") (pintype "bidirectional"))
    )
    (net (code "94") (name "GND") (class "Default")
      (node (ref "C1") (pin "-") (pinfunction "-_-") (pintype "passive"))
      (node (ref "C2") (pin "2") (pinfunction "2_2") (pintype "passive"))
      (node (ref "C3") (pin "-") (pinfunction "-_-") (pintype "passive"))
      (node (ref "C4") (pin "-") (pinfunction "-_-") (pintype "passive"))
      (node (ref "C6") (pin "-") (pinfunction "-_-") (pintype "passive"))
      (node (ref "D13") (pin "C") (pinfunction "C_C") (pintype "passive"))
      (node (ref "J1") (pin "2") (pinfunction "2_2") (pintype "passive"))
      (node (ref "JP1") (pin "2") (pinfunction "2_2") (pintype "passive"))
      (node (ref "JP11") (pin "4") (pinfunction "4_4") (pintype "passive"))
      (node (ref "JP11") (pin "5") (pinfunction "5_5") (pintype "passive"))
      (node (ref "JP15") (pin "6") (pinfunction "6_6") (pintype "passive"))
      (node (ref "PWR") (pin "C") (pinfunction "C_C") (pintype "passive"))
      (node (ref "R1") (pin "2") (pinfunction "2_2") (pintype "passive"))
      (node (ref "R5") (pin "2") (pinfunction "2_2") (pintype "passive"))
      (node (ref "R8") (pin "2") (pinfunction "2_2") (pintype "passive"))
      (node (ref "RN5") (pin "6") (pinfunction "2_6") (pintype "passive"))
      (node (ref "RN5") (pin "7") (pinfunction "2_7") (pintype "passive"))
      (node (ref "RN5") (pin "8") (pinfunction "2_8") (pintype "passive"))
      (node (ref "S2") (pin "1") (pinfunction "1_1") (pintype "passive"))
      (node (ref "S2") (pin "2") (pinfunction "2_2") (pintype "passive"))
      (node (ref "SER1") (pin "1") (pinfunction "1_1") (pintype "passive"))
      (node (ref "SER2") (pin "1") (pinfunction "1_1") (pintype "passive"))
      (node (ref "TFT") (pin "1") (pinfunction "1_1") (pintype "passive"))
      (node (ref "T_STP") (pin "C") (pinfunction "C_C") (pintype "passive"))
      (node (ref "U$1") (pin "GND") (pinfunction "GND_GND") (pintype "power_in"))
      (node (ref "U$1") (pin "GND@0") (pinfunction "GND_GND@0") (pintype "power_in"))
      (node (ref "U$6") (pin "GND") (pinfunction "GND_GND") (pintype "power_in"))
      (node (ref "U$6") (pin "GND@0") (pinfunction "GND_GND@0") (pintype "power_in"))
      (node (ref "U$7") (pin "GND") (pinfunction "GND_GND") (pintype "power_in"))
      (node (ref "U$7") (pin "GND@0") (pinfunction "GND_GND@0") (pintype "power_in"))
      (node (ref "U1") (pin "GND@0") (pinfunction "GND_GND@0") (pintype "power_in"))
      (node (ref "U1") (pin "GND@1") (pinfunction "GND_GND@1") (pintype "power_in"))
      (node (ref "U1") (pin "GND@2") (pinfunction "GND_GND@2") (pintype "power_in"))
      (node (ref "U1") (pin "GND@3") (pinfunction "GND_GND@3") (pintype "power_in"))
      (node (ref "U1") (pin "GND@4") (pinfunction "GND_GND@4") (pintype "power_in"))
      (node (ref "X1") (pin "RING") (pinfunction "RING_RING") (pintype "bidirectional"))
      (node (ref "X1") (pin "RING_SW") (pinfunction "RING_SW_RING_SW") (pintype "bidirectional"))
      (node (ref "X_STP") (pin "C") (pinfunction "C_C") (pintype "passive"))
      (node (ref "Y_STP") (pin "C") (pinfunction "C_C") (pintype "passive"))
    )
    (net (code "95") (name "Net-(JP2-Pad1)") (class "Default")
      (node (ref "JP2") (pin "1") (pinfunction "1_1") (pintype "passive"))
      (node (ref "U$6") (pin "2B") (pinfunction "2B_2B") (pintype "output"))
      (node (ref "X-MOT") (pin "1") (pinfunction "1_1") (pintype "bidirectional"))
    )
    (net (code "96") (name "Net-(JP2-Pad2)") (class "Default")
      (node (ref "JP2") (pin "2") (pinfunction "2_2") (pintype "passive"))
      (node (ref "U$6") (pin "2A") (pinfunction "2A_2A") (pintype "output"))
      (node (ref "X-MOT") (pin "2") (pinfunction "2_2") (pintype "bidirectional"))
    )
    (net (code "97") (name "Net-(JP2-Pad3)") (class "Default")
      (node (ref "JP2") (pin "3") (pinfunction "3_3") (pintype "passive"))
      (node (ref "U$6") (pin "1A") (pinfunction "1A_1A") (pintype "output"))
      (node (ref "X-MOT") (pin "3") (pinfunction "3_3") (pintype "bidirectional"))
    )
    (net (code "98") (name "Net-(JP2-Pad4)") (class "Default")
      (node (ref "JP2") (pin "4") (pinfunction "4_4") (pintype "passive"))
      (node (ref "U$6") (pin "1B") (pinfunction "1B_1B") (pintype "output"))
      (node (ref "X-MOT") (pin "4") (pinfunction "4_4") (pintype "bidirectional"))
    )
    (net (code "99") (name "Net-(JP5-Pad1)") (class "Default")
      (node (ref "JP5") (pin "1") (pinfunction "1_1") (pintype "passive"))
      (node (ref "U$1") (pin "2B") (pinfunction "2B_2B") (pintype "output"))
      (node (ref "Z-MOT1") (pin "1") (pinfunction "1_1") (pintype "bidirectional"))
    )
    (net (code "100") (name "Net-(JP5-Pad2)") (class "Default")
      (node (ref "JP5") (pin "2") (pinfunction "2_2") (pintype "passive"))
      (node (ref "U$1") (pin "2A") (pinfunction "2A_2A") (pintype "output"))
      (node (ref "Z-MOT1") (pin "2") (pinfunction "2_2") (pintype "bidirectional"))
    )
    (net (code "101") (name "Net-(JP5-Pad3)") (class "Default")
      (node (ref "JP5") (pin "3") (pinfunction "3_3") (pintype "passive"))
      (node (ref "U$1") (pin "1A") (pinfunction "1A_1A") (pintype "output"))
      (node (ref "Z-MOT1") (pin "3") (pinfunction "3_3") (pintype "bidirectional"))
    )
    (net (code "102") (name "Net-(JP5-Pad4)") (class "Default")
      (node (ref "JP5") (pin "4") (pinfunction "4_4") (pintype "passive"))
      (node (ref "U$1") (pin "1B") (pinfunction "1B_1B") (pintype "output"))
      (node (ref "Z-MOT1") (pin "4") (pinfunction "4_4") (pintype "bidirectional"))
    )
    (net (code "103") (name "Net-(JP7-Pad1)") (class "Default")
      (node (ref "JP7") (pin "1") (pinfunction "1_1") (pintype "passive"))
      (node (ref "U$7") (pin "2B") (pinfunction "2B_2B") (pintype "output"))
      (node (ref "Y-MOT") (pin "1") (pinfunction "1_1") (pintype "bidirectional"))
    )
    (net (code "104") (name "Net-(JP7-Pad2)") (class "Default")
      (node (ref "JP7") (pin "2") (pinfunction "2_2") (pintype "passive"))
      (node (ref "U$7") (pin "2A") (pinfunction "2A_2A") (pintype "output"))
      (node (ref "Y-MOT") (pin "2") (pinfunction "2_2") (pintype "bidirectional"))
    )
    (net (code "105") (name "Net-(JP7-Pad3)") (class "Default")
      (node (ref "JP7") (pin "3") (pinfunction "3_3") (pintype "passive"))
      (node (ref "U$7") (pin "1A") (pinfunction "1A_1A") (pintype "output"))
      (node (ref "Y-MOT") (pin "3") (pinfunction "3_3") (pintype "bidirectional"))
    )
    (net (code "106") (name "Net-(JP7-Pad4)") (class "Default")
      (node (ref "JP7") (pin "4") (pinfunction "4_4") (pintype "passive"))
      (node (ref "U$7") (pin "1B") (pinfunction "1B_1B") (pintype "output"))
      (node (ref "Y-MOT") (pin "4") (pinfunction "4_4") (pintype "bidirectional"))
    )
    (net (code "107") (name "Net-(R1-Pad1)") (class "Default")
      (node (ref "R1") (pin "1") (pinfunction "1_1") (pintype "passive"))
      (node (ref "SJ7") (pin "2") (pinfunction "2_2") (pintype "passive"))
      (node (ref "U$1") (pin "MS1") (pinfunction "MS1_MS1") (pintype "input"))
    )
    (net (code "108") (name "Net-(R3-Pad1)") (class "Default")
      (node (ref "R3") (pin "1") (pinfunction "1_1") (pintype "passive"))
      (node (ref "T_STP") (pin "A") (pinfunction "A_A") (pintype "passive"))
    )
    (net (code "109") (name "Net-(R5-Pad1)") (class "Default")
      (node (ref "R5") (pin "1") (pinfunction "1_1") (pintype "passive"))
      (node (ref "SJ1") (pin "2") (pinfunction "2_2") (pintype "passive"))
      (node (ref "U$6") (pin "MS1") (pinfunction "MS1_MS1") (pintype "input"))
    )
    (net (code "110") (name "Net-(R6-Pad1)") (class "Default")
      (node (ref "R6") (pin "1") (pinfunction "1_1") (pintype "passive"))
      (node (ref "X_STP") (pin "A") (pinfunction "A_A") (pintype "passive"))
    )
    (net (code "111") (name "Net-(R8-Pad1)") (class "Default")
      (node (ref "R8") (pin "1") (pinfunction "1_1") (pintype "passive"))
      (node (ref "SJ3") (pin "2") (pinfunction "2_2") (pintype "passive"))
      (node (ref "U$7") (pin "MS1") (pinfunction "MS1_MS1") (pintype "input"))
    )
    (net (code "112") (name "Net-(RN6-Pad1)") (class "Default")
      (node (ref "RN6") (pin "1") (pinfunction "1_1") (pintype "passive"))
      (node (ref "Y_STP") (pin "A") (pinfunction "A_A") (pintype "passive"))
    )
    (net (code "113") (name "Net-(RN6B-1)") (class "Default")
      (node (ref "RN6") (pin "2") (pinfunction "1_2") (pintype "passive"))
      (node (ref "RX_LED") (pin "C") (pinfunction "C_C") (pintype "passive"))
    )
    (net (code "114") (name "Net-(RN6C-1)") (class "Default")
      (node (ref "RN6") (pin "3") (pinfunction "1_3") (pintype "passive"))
      (node (ref "TX_LED") (pin "C") (pinfunction "C_C") (pintype "passive"))
    )
    (net (code "115") (name "Net-(RN6D-1)") (class "Default")
      (node (ref "PWR") (pin "A") (pinfunction "A_A") (pintype "passive"))
      (node (ref "RN6") (pin "4") (pinfunction "1_4") (pintype "passive"))
    )
    (net (code "116") (name "Net-(SJ2-Pad2)") (class "Default")
      (node (ref "SJ2") (pin "2") (pinfunction "2_2") (pintype "passive"))
      (node (ref "U$6") (pin "MS2") (pinfunction "MS2_MS2") (pintype "input"))
    )
    (net (code "117") (name "Net-(SJ4-Pad2)") (class "Default")
      (node (ref "SJ4") (pin "2") (pinfunction "2_2") (pintype "passive"))
      (node (ref "U$7") (pin "MS2") (pinfunction "MS2_MS2") (pintype "input"))
    )
    (net (code "118") (name "Net-(SJ5-Pad2)") (class "Default")
      (node (ref "SJ5") (pin "2") (pinfunction "2_2") (pintype "passive"))
      (node (ref "U$6") (pin "MS3") (pinfunction "MS3_MS3") (pintype "input"))
    )
    (net (code "119") (name "Net-(SJ6-Pad2)") (class "Default")
      (node (ref "SJ6") (pin "2") (pinfunction "2_2") (pintype "passive"))
      (node (ref "U$7") (pin "MS3") (pinfunction "MS3_MS3") (pintype "input"))
    )
    (net (code "120") (name "Net-(SJ8-Pad2)") (class "Default")
      (node (ref "SJ8") (pin "2") (pinfunction "2_2") (pintype "passive"))
      (node (ref "U$1") (pin "MS2") (pinfunction "MS2_MS2") (pintype "input"))
    )
    (net (code "121") (name "Net-(SJ9-Pad2)") (class "Default")
      (node (ref "SJ9") (pin "2") (pinfunction "2_2") (pintype "passive"))
      (node (ref "U$1") (pin "MS3") (pinfunction "MS3_MS3") (pintype "input"))
    )
    (net (code "122") (name "Net-(U$1-SLEEP)") (class "Default")
      (node (ref "U$1") (pin "RST") (pinfunction "RST_RST") (pintype "input"))
      (node (ref "U$1") (pin "SLP") (pinfunction "SLEEP_SLP") (pintype "input"))
    )
    (net (code "123") (name "Net-(U$6-SLEEP)") (class "Default")
      (node (ref "U$6") (pin "RST") (pinfunction "RST_RST") (pintype "input"))
      (node (ref "U$6") (pin "SLP") (pinfunction "SLEEP_SLP") (pintype "input"))
    )
    (net (code "124") (name "Net-(U$7-SLEEP)") (class "Default")
      (node (ref "U$7") (pin "RST") (pinfunction "RST_RST") (pintype "input"))
      (node (ref "U$7") (pin "SLP") (pinfunction "SLEEP_SLP") (pintype "input"))
    )
    (net (code "125") (name "VCC") (class "Default")
      (node (ref "JP11") (pin "3") (pinfunction "3_3") (pintype "passive"))
      (node (ref "JP15") (pin "5") (pinfunction "5_5") (pintype "passive"))
      (node (ref "R18") (pin "1") (pinfunction "1_1") (pintype "passive"))
      (node (ref "R19") (pin "1") (pinfunction "1_1") (pintype "passive"))
      (node (ref "R2") (pin "1") (pinfunction "1_1") (pintype "passive"))
      (node (ref "RN6") (pin "5") (pinfunction "2_5") (pintype "passive"))
      (node (ref "RX_LED") (pin "A") (pinfunction "A_A") (pintype "passive"))
      (node (ref "SER1") (pin "2") (pinfunction "2_2") (pintype "passive"))
      (node (ref "SER2") (pin "2") (pinfunction "2_2") (pintype "passive"))
      (node (ref "SJ1") (pin "1") (pinfunction "1_1") (pintype "passive"))
      (node (ref "SJ2") (pin "1") (pinfunction "1_1") (pintype "passive"))
      (node (ref "SJ3") (pin "1") (pinfunction "1_1") (pintype "passive"))
      (node (ref "SJ4") (pin "1") (pinfunction "1_1") (pintype "passive"))
      (node (ref "SJ5") (pin "1") (pinfunction "1_1") (pintype "passive"))
      (node (ref "SJ6") (pin "1") (pinfunction "1_1") (pintype "passive"))
      (node (ref "SJ7") (pin "1") (pinfunction "1_1") (pintype "passive"))
      (node (ref "SJ8") (pin "1") (pinfunction "1_1") (pintype "passive"))
      (node (ref "SJ9") (pin "1") (pinfunction "1_1") (pintype "passive"))
      (node (ref "TFT") (pin "3") (pinfunction "3_3") (pintype "passive"))
      (node (ref "TX_LED") (pin "A") (pinfunction "A_A") (pintype "passive"))
      (node (ref "U$1") (pin "VDD") (pinfunction "VDD_VDD") (pintype "power_in"))
      (node (ref "U$6") (pin "VDD") (pinfunction "VDD_VDD") (pintype "power_in"))
      (node (ref "U$7") (pin "VDD") (pinfunction "VDD_VDD") (pintype "power_in"))
      (node (ref "U1") (pin "5V@0") (pinfunction "5V_5V@0") (pintype "power_in"))
      (node (ref "U1") (pin "5V@1") (pinfunction "5V_5V@1") (pintype "power_in"))
      (node (ref "U1") (pin "5V@2") (pinfunction "5V_5V@2") (pintype "power_in"))
    )
    (net (code "126") (name "unconnected-(TFT-Pad2)") (class "Default")
      (node (ref "TFT") (pin "2") (pinfunction "2_2") (pintype "passive"))
    )
    (net (code "127") (name "unconnected-(TFT-Pad4)") (class "Default")
      (node (ref "TFT") (pin "4") (pinfunction "4_4") (pintype "passive"))
    )
    (net (code "128") (name "unconnected-(TFT-Pad5)") (class "Default")
      (node (ref "TFT") (pin "5") (pinfunction "5_5") (pintype "passive"))
    )
    (net (code "129") (name "unconnected-(TFT-Pad6)") (class "Default")
      (node (ref "TFT") (pin "6") (pinfunction "6_6") (pintype "passive"))
    )
    (net (code "130") (name "unconnected-(TFT-Pad8)") (class "Default")
      (node (ref "TFT") (pin "8") (pinfunction "8_8") (pintype "passive"))
    )
    (net (code "131") (name "unconnected-(TFT-Pad10)") (class "Default")
      (node (ref "TFT") (pin "10") (pinfunction "10_10") (pintype "passive"))
    )
    (net (code "132") (name "unconnected-(TFT-Pad12)") (class "Default")
      (node (ref "TFT") (pin "12") (pinfunction "12_12") (pintype "passive"))
    )
    (net (code "133") (name "unconnected-(TFT-Pad14)") (class "Default")
      (node (ref "TFT") (pin "14") (pinfunction "14_14") (pintype "passive"))
    )
    (net (code "134") (name "unconnected-(TFT-Pad16)") (class "Default")
      (node (ref "TFT") (pin "16") (pinfunction "16_16") (pintype "passive"))
    )
    (net (code "135") (name "unconnected-(TFT-Pad24)") (class "Default")
      (node (ref "TFT") (pin "24") (pinfunction "24_24") (pintype "passive"))
    )
    (net (code "136") (name "unconnected-(TFT-Pad31)") (class "Default")
      (node (ref "TFT") (pin "31") (pinfunction "31_31") (pintype "passive"))
    )
    (net (code "137") (name "unconnected-(TFT-Pad35)") (class "Default")
      (node (ref "TFT") (pin "35") (pinfunction "35_35") (pintype "passive"))
    )
    (net (code "138") (name "unconnected-(TFT-Pad38)") (class "Default")
      (node (ref "TFT") (pin "38") (pinfunction "38_38") (pintype "passive"))
    )
    (net (code "139") (name "unconnected-(TFT-Pad39)") (class "Default")
      (node (ref "TFT") (pin "39") (pinfunction "39_39") (pintype "passive"))
    )
    (net (code "140") (name "unconnected-(TFT-Pad40)") (class "Default")
      (node (ref "TFT") (pin "40") (pinfunction "40_40") (pintype "passive"))
    )
  )
)
